# due_alternative.net
KiCad netlist of a schematic drawn in EAGLE
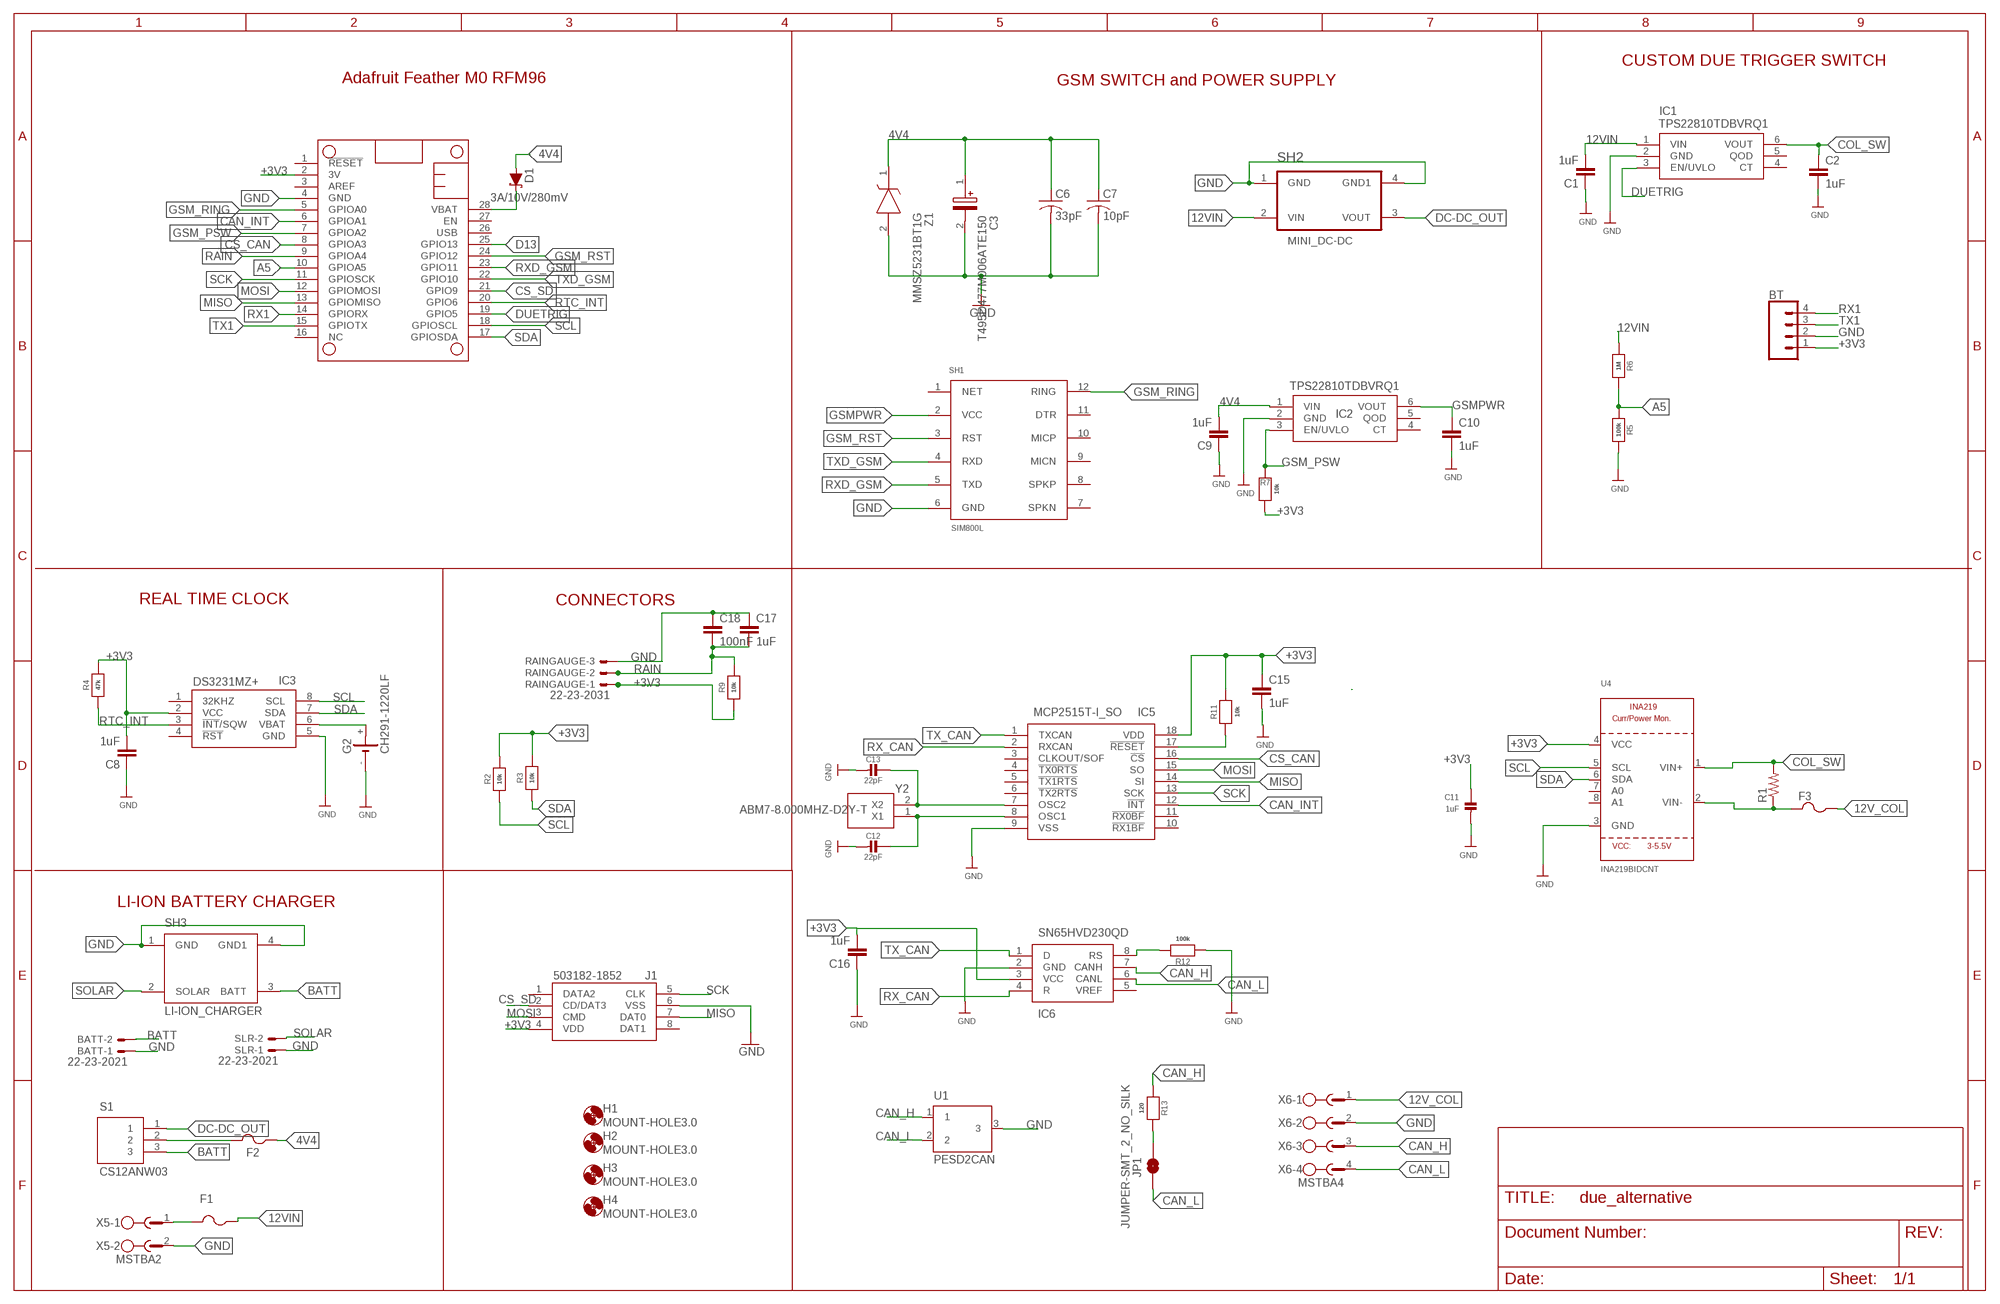
[diagram p0: schematic, sheet 1]

(export (version "E")
  (design (tool "Eeschema 10.0.6"))
  (components
    (comp (ref "BATT")
      (value "22-23-2021")
      (footprint "eagle-import:22-23-2021")
      (fields (field (name "MF") "MOLEX"))
      (libsource (lib "eagle-import") (part "22-23-2021"))
    )
    (comp (ref "BT")
      (value "CONN_04PTH")
      (footprint "eagle-import:1X04")
      (libsource (lib "eagle-import") (part "CONN_04PTH"))
    )
    (comp (ref "C1")
      (value "1uF")
      (footprint "eagle-import:C0603")
      (libsource (lib "eagle-import") (part "CC0603"))
    )
    (comp (ref "C2")
      (value "1uF")
      (footprint "eagle-import:C0603")
      (libsource (lib "eagle-import") (part "CC0603"))
    )
    (comp (ref "C3")
      (value "T495D477M006ATE150")
      (footprint "eagle-import:CAPPM7343X310N")
      (fields (field (name "MOUSER_PART_NUMBER") "80-T495D477M6ATE150"))
      (libsource (lib "eagle-import") (part "T495D477M006ATE150"))
    )
    (comp (ref "C6")
      (value "33pF")
      (footprint "eagle-import:C0603")
      (libsource (lib "eagle-import") (part "C-USC0603"))
    )
    (comp (ref "C7")
      (value "10pF")
      (footprint "eagle-import:C0603")
      (libsource (lib "eagle-import") (part "C-USC0603"))
    )
    (comp (ref "C8")
      (value "1uF")
      (footprint "eagle-import:C0603")
      (libsource (lib "eagle-import") (part "CC0603"))
    )
    (comp (ref "C9")
      (value "1uF")
      (footprint "eagle-import:C0603")
      (libsource (lib "eagle-import") (part "CC0603"))
    )
    (comp (ref "C10")
      (value "1uF")
      (footprint "eagle-import:C0603")
      (libsource (lib "eagle-import") (part "CC0603"))
    )
    (comp (ref "C11")
      (value "1uF")
      (footprint "eagle-import:0603-NO")
      (libsource (lib "eagle-import") (part "CAP_CERAMIC0603_NO"))
    )
    (comp (ref "C12")
      (value "22pF")
      (footprint "eagle-import:0603-NO")
      (libsource (lib "eagle-import") (part "CAP_CERAMIC0603_NO"))
    )
    (comp (ref "C13")
      (value "22pF")
      (footprint "eagle-import:0603-NO")
      (libsource (lib "eagle-import") (part "CAP_CERAMIC0603_NO"))
    )
    (comp (ref "C15")
      (value "1uF")
      (footprint "eagle-import:C0603")
      (libsource (lib "eagle-import") (part "CC0603"))
    )
    (comp (ref "C16")
      (value "1uF")
      (footprint "eagle-import:C0603")
      (libsource (lib "eagle-import") (part "CC0603"))
    )
    (comp (ref "C17")
      (value "1uF")
      (footprint "eagle-import:C0603")
      (libsource (lib "eagle-import") (part "CC0603"))
    )
    (comp (ref "C18")
      (value "100nF")
      (footprint "eagle-import:C0603")
      (libsource (lib "eagle-import") (part "CC0603"))
    )
    (comp (ref "D1")
      (value "3A/10V/280mV")
      (footprint "eagle-import:SOD-323")
      (libsource (lib "eagle-import") (part "DIODE-SCHOTTKY-BAT60A"))
    )
    (comp (ref "F1")
      (value "PTCFUSE-1206")
      (footprint "eagle-import:R1206")
      (libsource (lib "eagle-import") (part "PTCFUSE-1206"))
    )
    (comp (ref "F2")
      (value "PTCFUSE-1206")
      (footprint "eagle-import:R1206")
      (libsource (lib "eagle-import") (part "PTCFUSE-1206"))
    )
    (comp (ref "F3")
      (value "PTCFUSE-1206")
      (footprint "eagle-import:R1206")
      (libsource (lib "eagle-import") (part "PTCFUSE-1206"))
    )
    (comp (ref "G2")
      (value "CH291-1220LF")
      (footprint "eagle-import:CH291-1220LF")
      (libsource (lib "eagle-import") (part "CH291-1220LF"))
    )
    (comp (ref "H1")
      (value "MOUNT-HOLE3.0")
      (footprint "eagle-import:3,0")
      (libsource (lib "eagle-import") (part "MOUNT-HOLE3.0"))
    )
    (comp (ref "H2")
      (value "MOUNT-HOLE3.0")
      (footprint "eagle-import:3,0")
      (libsource (lib "eagle-import") (part "MOUNT-HOLE3.0"))
    )
    (comp (ref "H3")
      (value "MOUNT-HOLE3.0")
      (footprint "eagle-import:3,0")
      (libsource (lib "eagle-import") (part "MOUNT-HOLE3.0"))
    )
    (comp (ref "H4")
      (value "MOUNT-HOLE3.0")
      (footprint "eagle-import:3,0")
      (libsource (lib "eagle-import") (part "MOUNT-HOLE3.0"))
    )
    (comp (ref "IC1")
      (value "TPS22810TDBVRQ1")
      (footprint "eagle-import:SOT95P280X145-6N")
      (libsource (lib "eagle-import") (part "TPS22810TDBVRQ1"))
    )
    (comp (ref "IC2")
      (value "TPS22810TDBVRQ1")
      (footprint "eagle-import:SOT95P280X145-6N")
      (libsource (lib "eagle-import") (part "TPS22810TDBVRQ1"))
    )
    (comp (ref "IC3")
      (value "DS3231MZ+")
      (footprint "eagle-import:SOIC127P600X175-8N")
      (fields (field (name "RS_PART_NUMBER") "1897249"))
      (libsource (lib "eagle-import") (part "DS3231MZ+"))
    )
    (comp (ref "IC5")
      (value "MCP2515T-I_SO")
      (footprint "eagle-import:SOIC127P1030X265-18N")
      (fields
        (field (name "MANUFACTURER_PART_NUMBER") "MCP2515T-I/SO")
        (field (name "MOUSER_PART_NUMBER") "579-MCP2515T-I/SO")
      )
      (libsource (lib "eagle-import") (part "MCP2515T-I_SO"))
    )
    (comp (ref "IC6")
      (value "SN65HVD230QD")
      (footprint "eagle-import:SOIC127P600X175-8N")
      (fields (field (name "MOUSER_PART_NUMBER") "595-SN65HVD230QD"))
      (libsource (lib "eagle-import") (part "SN65HVD230QD"))
    )
    (comp (ref "J1")
      (value "503182-1852")
      (footprint "eagle-import:5031821852")
      (fields (field (name "MOUSER_PART_NUMBER") "538-503182-1852"))
      (libsource (lib "eagle-import") (part "503182-1852"))
    )
    (comp (ref "JP1")
      (value "JUMPER-SMT_2_NO_SILK")
      (footprint "eagle-import:SMT-JUMPER_2_NO_SILK")
      (libsource (lib "eagle-import") (part "JUMPER-SMT_2_NO_SILK"))
    )
    (comp (ref "MS1")
      (value "FEATHERWING_NODIM")
      (footprint "eagle-import:FEATHERWING_DIM")
      (libsource (lib "eagle-import") (part "FEATHERWING_NODIM"))
    )
    (comp (ref "R1")
      (value "R-US_R6332")
      (footprint "eagle-import:R6332")
      (libsource (lib "eagle-import") (part "R-US_R6332"))
    )
    (comp (ref "R2")
      (value "10k")
      (footprint "eagle-import:0603-NO")
      (libsource (lib "eagle-import") (part "RESISTOR_0603_NOOUT"))
    )
    (comp (ref "R3")
      (value "10k")
      (footprint "eagle-import:0603-NO")
      (libsource (lib "eagle-import") (part "RESISTOR_0603_NOOUT"))
    )
    (comp (ref "R4")
      (value "47k")
      (footprint "eagle-import:0603-NO")
      (libsource (lib "eagle-import") (part "RESISTOR_0603_NOOUT"))
    )
    (comp (ref "R5")
      (value "100k")
      (footprint "eagle-import:0603-NO")
      (libsource (lib "eagle-import") (part "RESISTOR_0603_NOOUT"))
    )
    (comp (ref "R6")
      (value "1M")
      (footprint "eagle-import:0603-NO")
      (libsource (lib "eagle-import") (part "RESISTOR_0603_NOOUT"))
    )
    (comp (ref "R7")
      (value "10k")
      (footprint "eagle-import:0603-NO")
      (libsource (lib "eagle-import") (part "RESISTOR_0603_NOOUT"))
    )
    (comp (ref "R9")
      (value "10k")
      (footprint "eagle-import:0603-NO")
      (libsource (lib "eagle-import") (part "RESISTOR_0603_NOOUT"))
    )
    (comp (ref "R11")
      (value "10k")
      (footprint "eagle-import:0603-NO")
      (libsource (lib "eagle-import") (part "RESISTOR_0603_NOOUT"))
    )
    (comp (ref "R12")
      (value "100k")
      (footprint "eagle-import:0603-NO")
      (libsource (lib "eagle-import") (part "RESISTOR_0603_NOOUT"))
    )
    (comp (ref "R13")
      (value "120")
      (footprint "eagle-import:0603-NO")
      (libsource (lib "eagle-import") (part "RESISTOR_0603_NOOUT"))
    )
    (comp (ref "RAINGAUGE")
      (value "22-23-2031")
      (footprint "eagle-import:22-23-2031")
      (fields (field (name "MF") "MOLEX"))
      (libsource (lib "eagle-import") (part "22-23-2031"))
    )
    (comp (ref "S1")
      (value "CS12ANW03")
      (footprint "eagle-import:CS12ANW03")
      (fields (field (name "MOUSER_PART_NUMBER") "633-CS12ANW03"))
      (libsource (lib "eagle-import") (part "CS12ANW03"))
    )
    (comp (ref "SH1")
      (value "SIM800L")
      (footprint "eagle-import:GSM_SIM800L")
      (libsource (lib "eagle-import") (part "SIM800L"))
    )
    (comp (ref "SH2")
      (value "MINI_DC-DC")
      (footprint "eagle-import:MINI_DC-DC_MP2307DN")
      (libsource (lib "eagle-import") (part "MINI_DC-DC"))
    )
    (comp (ref "SH3")
      (value "LI-ION_CHARGER")
      (footprint "eagle-import:LI-ION_CHARGER")
      (libsource (lib "eagle-import") (part "LI-ION_CHARGER"))
    )
    (comp (ref "SLR")
      (value "22-23-2021")
      (footprint "eagle-import:22-23-2021")
      (fields (field (name "MF") "MOLEX"))
      (libsource (lib "eagle-import") (part "22-23-2021"))
    )
    (comp (ref "U1")
      (value "PESD2CAN")
      (footprint "eagle-import:SOT23")
      (libsource (lib "eagle-import") (part "PESD2CAN"))
    )
    (comp (ref "U4")
      (value "INA219BIDCNT")
      (footprint "eagle-import:SOT23-8")
      (libsource (lib "eagle-import") (part "INA219"))
    )
    (comp (ref "X5")
      (value "MSTBA2")
      (footprint "eagle-import:MSTBA2")
      (fields (field (name "MF") "FARNELL") (field (name "MPN") "1757242"))
      (libsource (lib "eagle-import") (part "MSTBA2"))
    )
    (comp (ref "X6")
      (value "MSTBA4")
      (footprint "eagle-import:MSTBA4")
      (fields (field (name "MF") "FARNELL") (field (name "MPN") "1757268"))
      (libsource (lib "eagle-import") (part "MSTBA4"))
    )
    (comp (ref "Y2")
      (value "ABM7-8.000MHZ-D2Y-T")
      (footprint "eagle-import:ABM78000MHZD2YT")
      (fields (field (name "MOUSER_PART_NUMBER") "815-ABM7-8-D2Y-T"))
      (libsource (lib "eagle-import") (part "ABM7-8.000MHZ-D2Y-T"))
    )
    (comp (ref "Z1")
      (value "MMSZ5231BT1G")
      (footprint "eagle-import:SOD3716X135N")
      (fields (field (name "RS_PART_NUMBER") "5453049P"))
      (libsource (lib "eagle-import") (part "MMSZ5231BT1G"))
    )
  )
  (nets
    (net (code "1") (name "+3V3") (class "Default")
      (node (ref "BT") (pin "1") (pinfunction "1_1") (pintype "passive"))
      (node (ref "C11") (pin "1") (pinfunction "1_1") (pintype "passive"))
      (node (ref "C15") (pin "1") (pinfunction "1_1") (pintype "passive"))
      (node (ref "C16") (pin "2") (pinfunction "2_2") (pintype "passive"))
      (node (ref "C8") (pin "2") (pinfunction "2_2") (pintype "passive"))
      (node (ref "IC3") (pin "2") (pinfunction "VCC_2") (pintype "power_in"))
      (node (ref "IC5") (pin "18") (pinfunction "VDD_18") (pintype "bidirectional"))
      (node (ref "IC6") (pin "3") (pinfunction "VCC_3") (pintype "bidirectional"))
      (node (ref "J1") (pin "4") (pinfunction "VDD_4") (pintype "bidirectional"))
      (node (ref "MS1") (pin "2") (pinfunction "3V_2") (pintype "power_in"))
      (node (ref "R11") (pin "2") (pinfunction "2_2") (pintype "passive"))
      (node (ref "R2") (pin "2") (pinfunction "2_2") (pintype "passive"))
      (node (ref "R3") (pin "2") (pinfunction "2_2") (pintype "passive"))
      (node (ref "R4") (pin "2") (pinfunction "2_2") (pintype "passive"))
      (node (ref "R7") (pin "1") (pinfunction "1_1") (pintype "passive"))
      (node (ref "R9") (pin "1") (pinfunction "1_1") (pintype "passive"))
      (node (ref "RAINGAUGE") (pin "1") (pinfunction "S_1") (pintype "passive"))
      (node (ref "U4") (pin "4") (pinfunction "VCC_4") (pintype "bidirectional"))
    )
    (net (code "2") (name "/USB") (class "Default")
      (node (ref "MS1") (pin "26") (pinfunction "USB_26") (pintype "power_in"))
    )
    (net (code "3") (name "4V4") (class "Default")
      (node (ref "C3") (pin "1") (pinfunction "+_1") (pintype "bidirectional"))
      (node (ref "C6") (pin "1") (pinfunction "1_1") (pintype "passive"))
      (node (ref "C7") (pin "1") (pinfunction "1_1") (pintype "passive"))
      (node (ref "C9") (pin "2") (pinfunction "2_2") (pintype "passive"))
      (node (ref "D1") (pin "A") (pinfunction "A_A") (pintype "passive"))
      (node (ref "F2") (pin "1") (pinfunction "1_1") (pintype "passive"))
      (node (ref "IC2") (pin "1") (pinfunction "VIN_1") (pintype "bidirectional"))
      (node (ref "Z1") (pin "1") (pinfunction "K_1") (pintype "bidirectional"))
    )
    (net (code "4") (name "12VIN") (class "Default")
      (node (ref "C1") (pin "2") (pinfunction "2_2") (pintype "passive"))
      (node (ref "F1") (pin "1") (pinfunction "1_1") (pintype "passive"))
      (node (ref "IC1") (pin "1") (pinfunction "VIN_1") (pintype "bidirectional"))
      (node (ref "R6") (pin "1") (pinfunction "1_1") (pintype "passive"))
      (node (ref "SH2") (pin "2") (pinfunction "VIN_2") (pintype "bidirectional"))
    )
    (net (code "5") (name "12V_COL") (class "Default")
      (node (ref "F3") (pin "1") (pinfunction "1_1") (pintype "passive"))
      (node (ref "X6") (pin "1") (pinfunction "1_1") (pintype "passive"))
    )
    (net (code "6") (name "A5") (class "Default")
      (node (ref "MS1") (pin "10") (pinfunction "GPIOA5_10") (pintype "bidirectional"))
      (node (ref "R5") (pin "1") (pinfunction "1_1") (pintype "passive"))
      (node (ref "R6") (pin "2") (pinfunction "2_2") (pintype "passive"))
    )
    (net (code "7") (name "BATT") (class "Default")
      (node (ref "BATT") (pin "2") (pinfunction "S_2") (pintype "passive"))
      (node (ref "S1") (pin "3") (pinfunction "3_3") (pintype "bidirectional"))
      (node (ref "SH3") (pin "3") (pinfunction "BATT_3") (pintype "bidirectional"))
    )
    (net (code "8") (name "CAN_H") (class "Default")
      (node (ref "IC6") (pin "7") (pinfunction "CANH_7") (pintype "bidirectional"))
      (node (ref "R13") (pin "1") (pinfunction "1_1") (pintype "passive"))
      (node (ref "U1") (pin "1") (pinfunction "1_1") (pintype "input"))
      (node (ref "X6") (pin "3") (pinfunction "1_3") (pintype "passive"))
    )
    (net (code "9") (name "CAN_INT") (class "Default")
      (node (ref "IC5") (pin "12") (pinfunction "~{INT}_12") (pintype "bidirectional"))
      (node (ref "MS1") (pin "6") (pinfunction "GPIOA1_6") (pintype "bidirectional"))
    )
    (net (code "10") (name "CAN_L") (class "Default")
      (node (ref "IC6") (pin "6") (pinfunction "CANL_6") (pintype "bidirectional"))
      (node (ref "JP1") (pin "1") (pinfunction "1_1") (pintype "passive"))
      (node (ref "U1") (pin "2") (pinfunction "2_2") (pintype "power_in"))
      (node (ref "X6") (pin "4") (pinfunction "1_4") (pintype "passive"))
    )
    (net (code "11") (name "COL_SW") (class "Default")
      (node (ref "C2") (pin "1") (pinfunction "1_1") (pintype "passive"))
      (node (ref "IC1") (pin "6") (pinfunction "VOUT_6") (pintype "bidirectional"))
      (node (ref "R1") (pin "2") (pinfunction "2_2") (pintype "passive"))
      (node (ref "U4") (pin "1") (pinfunction "VIN+_1") (pintype "bidirectional"))
    )
    (net (code "12") (name "CS_CAN") (class "Default")
      (node (ref "IC5") (pin "16") (pinfunction "~{CS}_16") (pintype "bidirectional"))
      (node (ref "MS1") (pin "8") (pinfunction "GPIOA3_8") (pintype "bidirectional"))
    )
    (net (code "13") (name "CS_SD") (class "Default")
      (node (ref "J1") (pin "2") (pinfunction "CD/DAT3_2") (pintype "bidirectional"))
      (node (ref "MS1") (pin "21") (pinfunction "GPIO9_21") (pintype "bidirectional"))
    )
    (net (code "14") (name "D13") (class "Default")
      (node (ref "MS1") (pin "25") (pinfunction "GPIO13_25") (pintype "bidirectional"))
    )
    (net (code "15") (name "DC-DC_OUT") (class "Default")
      (node (ref "S1") (pin "1") (pinfunction "1_1") (pintype "bidirectional"))
      (node (ref "SH2") (pin "3") (pinfunction "VOUT_3") (pintype "bidirectional"))
    )
    (net (code "16") (name "DUETRIG") (class "Default")
      (node (ref "IC1") (pin "3") (pinfunction "EN/UVLO_3") (pintype "bidirectional"))
      (node (ref "MS1") (pin "19") (pinfunction "GPIO5_19") (pintype "bidirectional"))
    )
    (net (code "17") (name "GND") (class "Default")
      (node (ref "BATT") (pin "1") (pinfunction "S_1") (pintype "passive"))
      (node (ref "BT") (pin "2") (pinfunction "2_2") (pintype "passive"))
      (node (ref "C1") (pin "1") (pinfunction "1_1") (pintype "passive"))
      (node (ref "C10") (pin "2") (pinfunction "2_2") (pintype "passive"))
      (node (ref "C11") (pin "2") (pinfunction "2_2") (pintype "passive"))
      (node (ref "C12") (pin "2") (pinfunction "2_2") (pintype "passive"))
      (node (ref "C13") (pin "2") (pinfunction "2_2") (pintype "passive"))
      (node (ref "C15") (pin "2") (pinfunction "2_2") (pintype "passive"))
      (node (ref "C16") (pin "1") (pinfunction "1_1") (pintype "passive"))
      (node (ref "C17") (pin "1") (pinfunction "1_1") (pintype "passive"))
      (node (ref "C18") (pin "1") (pinfunction "1_1") (pintype "passive"))
      (node (ref "C2") (pin "2") (pinfunction "2_2") (pintype "passive"))
      (node (ref "C3") (pin "2") (pinfunction "-_2") (pintype "bidirectional"))
      (node (ref "C6") (pin "2") (pinfunction "2_2") (pintype "passive"))
      (node (ref "C7") (pin "2") (pinfunction "2_2") (pintype "passive"))
      (node (ref "C8") (pin "1") (pinfunction "1_1") (pintype "passive"))
      (node (ref "C9") (pin "1") (pinfunction "1_1") (pintype "passive"))
      (node (ref "G2") (pin "-") (pinfunction "-_-") (pintype "passive"))
      (node (ref "IC1") (pin "2") (pinfunction "GND_2") (pintype "bidirectional"))
      (node (ref "IC2") (pin "2") (pinfunction "GND_2") (pintype "bidirectional"))
      (node (ref "IC3") (pin "5") (pinfunction "GND_5") (pintype "power_in"))
      (node (ref "IC5") (pin "9") (pinfunction "VSS_9") (pintype "bidirectional"))
      (node (ref "IC6") (pin "2") (pinfunction "GND_2") (pintype "bidirectional"))
      (node (ref "J1") (pin "6") (pinfunction "VSS_6") (pintype "bidirectional"))
      (node (ref "MS1") (pin "4") (pinfunction "GND_4") (pintype "power_in"))
      (node (ref "R12") (pin "1") (pinfunction "1_1") (pintype "passive"))
      (node (ref "R5") (pin "2") (pinfunction "2_2") (pintype "passive"))
      (node (ref "RAINGAUGE") (pin "3") (pinfunction "S_3") (pintype "passive"))
      (node (ref "SH1") (pin "6") (pinfunction "GND_6") (pintype "bidirectional"))
      (node (ref "SH2") (pin "1") (pinfunction "GND_1") (pintype "bidirectional"))
      (node (ref "SH2") (pin "4") (pinfunction "GND1_4") (pintype "bidirectional"))
      (node (ref "SH3") (pin "1") (pinfunction "GND_1") (pintype "bidirectional"))
      (node (ref "SH3") (pin "4") (pinfunction "GND1_4") (pintype "bidirectional"))
      (node (ref "SLR") (pin "1") (pinfunction "S_1") (pintype "passive"))
      (node (ref "U1") (pin "3") (pinfunction "3_3") (pintype "output"))
      (node (ref "U4") (pin "3") (pinfunction "GND_3") (pintype "bidirectional"))
      (node (ref "X5") (pin "2") (pinfunction "1_2") (pintype "passive"))
      (node (ref "X6") (pin "2") (pinfunction "1_2") (pintype "passive"))
      (node (ref "Z1") (pin "2") (pinfunction "A_2") (pintype "bidirectional"))
    )
    (net (code "18") (name "GSMPWR") (class "Default")
      (node (ref "C10") (pin "1") (pinfunction "1_1") (pintype "passive"))
      (node (ref "IC2") (pin "6") (pinfunction "VOUT_6") (pintype "bidirectional"))
      (node (ref "SH1") (pin "2") (pinfunction "VCC_2") (pintype "bidirectional"))
    )
    (net (code "19") (name "GSM_PSW") (class "Default")
      (node (ref "IC2") (pin "3") (pinfunction "EN/UVLO_3") (pintype "bidirectional"))
      (node (ref "MS1") (pin "7") (pinfunction "GPIOA2_7") (pintype "bidirectional"))
      (node (ref "R7") (pin "2") (pinfunction "2_2") (pintype "passive"))
    )
    (net (code "20") (name "GSM_RING") (class "Default")
      (node (ref "MS1") (pin "5") (pinfunction "GPIOA0_5") (pintype "bidirectional"))
      (node (ref "SH1") (pin "12") (pinfunction "RING_12") (pintype "bidirectional"))
    )
    (net (code "21") (name "GSM_RST") (class "Default")
      (node (ref "MS1") (pin "24") (pinfunction "GPIO12_24") (pintype "bidirectional"))
      (node (ref "SH1") (pin "3") (pinfunction "RST_3") (pintype "bidirectional"))
    )
    (net (code "22") (name "MISO") (class "Default")
      (node (ref "IC5") (pin "14") (pinfunction "SI_14") (pintype "bidirectional"))
      (node (ref "J1") (pin "7") (pinfunction "DAT0_7") (pintype "bidirectional"))
      (node (ref "MS1") (pin "13") (pinfunction "GPIOMISO_13") (pintype "bidirectional"))
    )
    (net (code "23") (name "MOSI") (class "Default")
      (node (ref "IC5") (pin "15") (pinfunction "SO_15") (pintype "bidirectional"))
      (node (ref "J1") (pin "3") (pinfunction "CMD_3") (pintype "bidirectional"))
      (node (ref "MS1") (pin "12") (pinfunction "GPIOMOSI_12") (pintype "bidirectional"))
    )
    (net (code "24") (name "Net-(F1-Pad2)") (class "Default")
      (node (ref "F1") (pin "2") (pinfunction "2_2") (pintype "passive"))
      (node (ref "X5") (pin "1") (pinfunction "1_1") (pintype "passive"))
    )
    (net (code "25") (name "Net-(F2-Pad2)") (class "Default")
      (node (ref "F2") (pin "2") (pinfunction "2_2") (pintype "passive"))
      (node (ref "S1") (pin "2") (pinfunction "2_2") (pintype "bidirectional"))
    )
    (net (code "26") (name "Net-(IC3-VBAT)") (class "Default")
      (node (ref "G2") (pin "+") (pinfunction "+_+") (pintype "passive"))
      (node (ref "IC3") (pin "6") (pinfunction "VBAT_6") (pintype "bidirectional"))
    )
    (net (code "27") (name "Net-(IC5-OSC1)") (class "Default")
      (node (ref "C12") (pin "1") (pinfunction "1_1") (pintype "passive"))
      (node (ref "IC5") (pin "8") (pinfunction "OSC1_8") (pintype "bidirectional"))
      (node (ref "Y2") (pin "1") (pinfunction "X1_1") (pintype "bidirectional"))
    )
    (net (code "28") (name "Net-(IC5-OSC2)") (class "Default")
      (node (ref "C13") (pin "1") (pinfunction "1_1") (pintype "passive"))
      (node (ref "IC5") (pin "7") (pinfunction "OSC2_7") (pintype "bidirectional"))
      (node (ref "Y2") (pin "2") (pinfunction "X2_2") (pintype "bidirectional"))
    )
    (net (code "29") (name "Net-(IC5-~{RESET})") (class "Default")
      (node (ref "IC5") (pin "17") (pinfunction "~{RESET}_17") (pintype "bidirectional"))
      (node (ref "R11") (pin "1") (pinfunction "1_1") (pintype "passive"))
    )
    (net (code "30") (name "Net-(IC6-RS)") (class "Default")
      (node (ref "IC6") (pin "8") (pinfunction "RS_8") (pintype "bidirectional"))
      (node (ref "R12") (pin "2") (pinfunction "2_2") (pintype "passive"))
    )
    (net (code "31") (name "Net-(JP1-Pad2)") (class "Default")
      (node (ref "JP1") (pin "2") (pinfunction "2_2") (pintype "passive"))
      (node (ref "R13") (pin "2") (pinfunction "2_2") (pintype "passive"))
    )
    (net (code "32") (name "Net-(MS1-VBAT)") (class "Default")
      (node (ref "D1") (pin "C") (pinfunction "C_C") (pintype "passive"))
      (node (ref "MS1") (pin "28") (pinfunction "VBAT_28") (pintype "power_in"))
    )
    (net (code "33") (name "Net-(U4-VIN-)") (class "Default")
      (node (ref "F3") (pin "2") (pinfunction "2_2") (pintype "passive"))
      (node (ref "R1") (pin "1") (pinfunction "1_1") (pintype "passive"))
      (node (ref "U4") (pin "2") (pinfunction "VIN-_2") (pintype "bidirectional"))
    )
    (net (code "34") (name "RAIN") (class "Default")
      (node (ref "C17") (pin "2") (pinfunction "2_2") (pintype "passive"))
      (node (ref "C18") (pin "2") (pinfunction "2_2") (pintype "passive"))
      (node (ref "MS1") (pin "9") (pinfunction "GPIOA4_9") (pintype "bidirectional"))
      (node (ref "R9") (pin "2") (pinfunction "2_2") (pintype "passive"))
      (node (ref "RAINGAUGE") (pin "2") (pinfunction "S_2") (pintype "passive"))
    )
    (net (code "35") (name "RTC_INT") (class "Default")
      (node (ref "IC3") (pin "3") (pinfunction "~{INT}/SQW_3") (pintype "input"))
      (node (ref "MS1") (pin "20") (pinfunction "GPIO6_20") (pintype "bidirectional"))
      (node (ref "R4") (pin "1") (pinfunction "1_1") (pintype "passive"))
    )
    (net (code "36") (name "RX1") (class "Default")
      (node (ref "BT") (pin "4") (pinfunction "4_4") (pintype "passive"))
      (node (ref "MS1") (pin "14") (pinfunction "GPIORX_14") (pintype "bidirectional"))
    )
    (net (code "37") (name "RXD_GSM") (class "Default")
      (node (ref "MS1") (pin "23") (pinfunction "GPIO11_23") (pintype "bidirectional"))
      (node (ref "SH1") (pin "5") (pinfunction "TXD_5") (pintype "bidirectional"))
    )
    (net (code "38") (name "RX_CAN") (class "Default")
      (node (ref "IC5") (pin "2") (pinfunction "RXCAN_2") (pintype "bidirectional"))
      (node (ref "IC6") (pin "4") (pinfunction "R_4") (pintype "bidirectional"))
    )
    (net (code "39") (name "SCK") (class "Default")
      (node (ref "IC5") (pin "13") (pinfunction "SCK_13") (pintype "bidirectional"))
      (node (ref "J1") (pin "5") (pinfunction "CLK_5") (pintype "bidirectional"))
      (node (ref "MS1") (pin "11") (pinfunction "GPIOSCK_11") (pintype "bidirectional"))
    )
    (net (code "40") (name "SCL") (class "Default")
      (node (ref "IC3") (pin "8") (pinfunction "SCL_8") (pintype "bidirectional"))
      (node (ref "MS1") (pin "18") (pinfunction "GPIOSCL_18") (pintype "bidirectional"))
      (node (ref "R2") (pin "1") (pinfunction "1_1") (pintype "passive"))
      (node (ref "U4") (pin "5") (pinfunction "SCL_5") (pintype "bidirectional"))
    )
    (net (code "41") (name "SDA") (class "Default")
      (node (ref "IC3") (pin "7") (pinfunction "SDA_7") (pintype "bidirectional"))
      (node (ref "MS1") (pin "17") (pinfunction "GPIOSDA_17") (pintype "bidirectional"))
      (node (ref "R3") (pin "1") (pinfunction "1_1") (pintype "passive"))
      (node (ref "U4") (pin "6") (pinfunction "SDA_6") (pintype "bidirectional"))
    )
    (net (code "42") (name "SOLAR") (class "Default")
      (node (ref "SH3") (pin "2") (pinfunction "SOLAR_2") (pintype "bidirectional"))
      (node (ref "SLR") (pin "2") (pinfunction "S_2") (pintype "passive"))
    )
    (net (code "43") (name "TX1") (class "Default")
      (node (ref "BT") (pin "3") (pinfunction "3_3") (pintype "passive"))
      (node (ref "MS1") (pin "15") (pinfunction "GPIOTX_15") (pintype "bidirectional"))
    )
    (net (code "44") (name "TXD_GSM") (class "Default")
      (node (ref "MS1") (pin "22") (pinfunction "GPIO10_22") (pintype "bidirectional"))
      (node (ref "SH1") (pin "4") (pinfunction "RXD_4") (pintype "bidirectional"))
    )
    (net (code "45") (name "TX_CAN") (class "Default")
      (node (ref "IC5") (pin "1") (pinfunction "TXCAN_1") (pintype "bidirectional"))
      (node (ref "IC6") (pin "1") (pinfunction "D_1") (pintype "bidirectional"))
    )
    (net (code "46") (name "unconnected-(IC1-CT-Pad4)") (class "Default")
      (node (ref "IC1") (pin "4") (pinfunction "CT_4") (pintype "bidirectional"))
    )
    (net (code "47") (name "unconnected-(IC1-QOD-Pad5)") (class "Default")
      (node (ref "IC1") (pin "5") (pinfunction "QOD_5") (pintype "bidirectional"))
    )
    (net (code "48") (name "unconnected-(IC2-CT-Pad4)") (class "Default")
      (node (ref "IC2") (pin "4") (pinfunction "CT_4") (pintype "bidirectional"))
    )
    (net (code "49") (name "unconnected-(IC2-QOD-Pad5)") (class "Default")
      (node (ref "IC2") (pin "5") (pinfunction "QOD_5") (pintype "bidirectional"))
    )
    (net (code "50") (name "unconnected-(IC3-32KHZ-Pad1)") (class "Default")
      (node (ref "IC3") (pin "1") (pinfunction "32KHZ_1") (pintype "bidirectional"))
    )
    (net (code "51") (name "unconnected-(IC3-~{RST}-Pad4)") (class "Default")
      (node (ref "IC3") (pin "4") (pinfunction "~{RST}_4") (pintype "input"))
    )
    (net (code "52") (name "unconnected-(IC5-CLKOUT{slash}SOF-Pad3)") (class "Default")
      (node (ref "IC5") (pin "3") (pinfunction "CLKOUT/SOF_3") (pintype "bidirectional"))
    )
    (net (code "53") (name "unconnected-(IC5-~{RX0BF}-Pad11)") (class "Default")
      (node (ref "IC5") (pin "11") (pinfunction "~{RX0BF}_11") (pintype "bidirectional"))
    )
    (net (code "54") (name "unconnected-(IC5-~{RX1BF}-Pad10)") (class "Default")
      (node (ref "IC5") (pin "10") (pinfunction "~{RX1BF}_10") (pintype "bidirectional"))
    )
    (net (code "55") (name "unconnected-(IC5-~{TX0RTS}-Pad4)") (class "Default")
      (node (ref "IC5") (pin "4") (pinfunction "~{TX0RTS}_4") (pintype "bidirectional"))
    )
    (net (code "56") (name "unconnected-(IC5-~{TX1RTS}-Pad5)") (class "Default")
      (node (ref "IC5") (pin "5") (pinfunction "~{TX1RTS}_5") (pintype "bidirectional"))
    )
    (net (code "57") (name "unconnected-(IC5-~{TX2RTS}-Pad6)") (class "Default")
      (node (ref "IC5") (pin "6") (pinfunction "~{TX2RTS}_6") (pintype "bidirectional"))
    )
    (net (code "58") (name "unconnected-(IC6-VREF-Pad5)") (class "Default")
      (node (ref "IC6") (pin "5") (pinfunction "VREF_5") (pintype "bidirectional"))
    )
    (net (code "59") (name "unconnected-(J1-DAT1-Pad8)") (class "Default")
      (node (ref "J1") (pin "8") (pinfunction "DAT1_8") (pintype "bidirectional"))
    )
    (net (code "60") (name "unconnected-(J1-DATA2-Pad1)") (class "Default")
      (node (ref "J1") (pin "1") (pinfunction "DATA2_1") (pintype "bidirectional"))
    )
    (net (code "61") (name "unconnected-(MS1-AREF-Pad3)") (class "Default")
      (node (ref "MS1") (pin "3") (pinfunction "AREF_3") (pintype "passive"))
    )
    (net (code "62") (name "unconnected-(MS1-EN-Pad27)") (class "Default")
      (node (ref "MS1") (pin "27") (pinfunction "EN_27") (pintype "passive"))
    )
    (net (code "63") (name "unconnected-(MS1-NC-Pad16)") (class "Default")
      (node (ref "MS1") (pin "16") (pinfunction "NC_16") (pintype "passive"))
    )
    (net (code "64") (name "unconnected-(MS1-~{RESET}-Pad1)") (class "Default")
      (node (ref "MS1") (pin "1") (pinfunction "~{RESET}_1") (pintype "input"))
    )
    (net (code "65") (name "unconnected-(SH1-DTR-Pad11)") (class "Default")
      (node (ref "SH1") (pin "11") (pinfunction "DTR_11") (pintype "bidirectional"))
    )
    (net (code "66") (name "unconnected-(SH1-MICN-Pad9)") (class "Default")
      (node (ref "SH1") (pin "9") (pinfunction "MICN_9") (pintype "bidirectional"))
    )
    (net (code "67") (name "unconnected-(SH1-MICP-Pad10)") (class "Default")
      (node (ref "SH1") (pin "10") (pinfunction "MICP_10") (pintype "bidirectional"))
    )
    (net (code "68") (name "unconnected-(SH1-NET-Pad1)") (class "Default")
      (node (ref "SH1") (pin "1") (pinfunction "NET_1") (pintype "bidirectional"))
    )
    (net (code "69") (name "unconnected-(SH1-SPKN-Pad7)") (class "Default")
      (node (ref "SH1") (pin "7") (pinfunction "SPKN_7") (pintype "bidirectional"))
    )
    (net (code "70") (name "unconnected-(SH1-SPKP-Pad8)") (class "Default")
      (node (ref "SH1") (pin "8") (pinfunction "SPKP_8") (pintype "bidirectional"))
    )
    (net (code "71") (name "unconnected-(U4-A0-Pad7)") (class "Default")
      (node (ref "U4") (pin "7") (pinfunction "A0_7") (pintype "bidirectional"))
    )
    (net (code "72") (name "unconnected-(U4-A1-Pad8)") (class "Default")
      (node (ref "U4") (pin "8") (pinfunction "A1_8") (pintype "bidirectional"))
    )
  )
)
